# SPISensors.net
KiCad netlist of a schematic drawn in Altium Designer
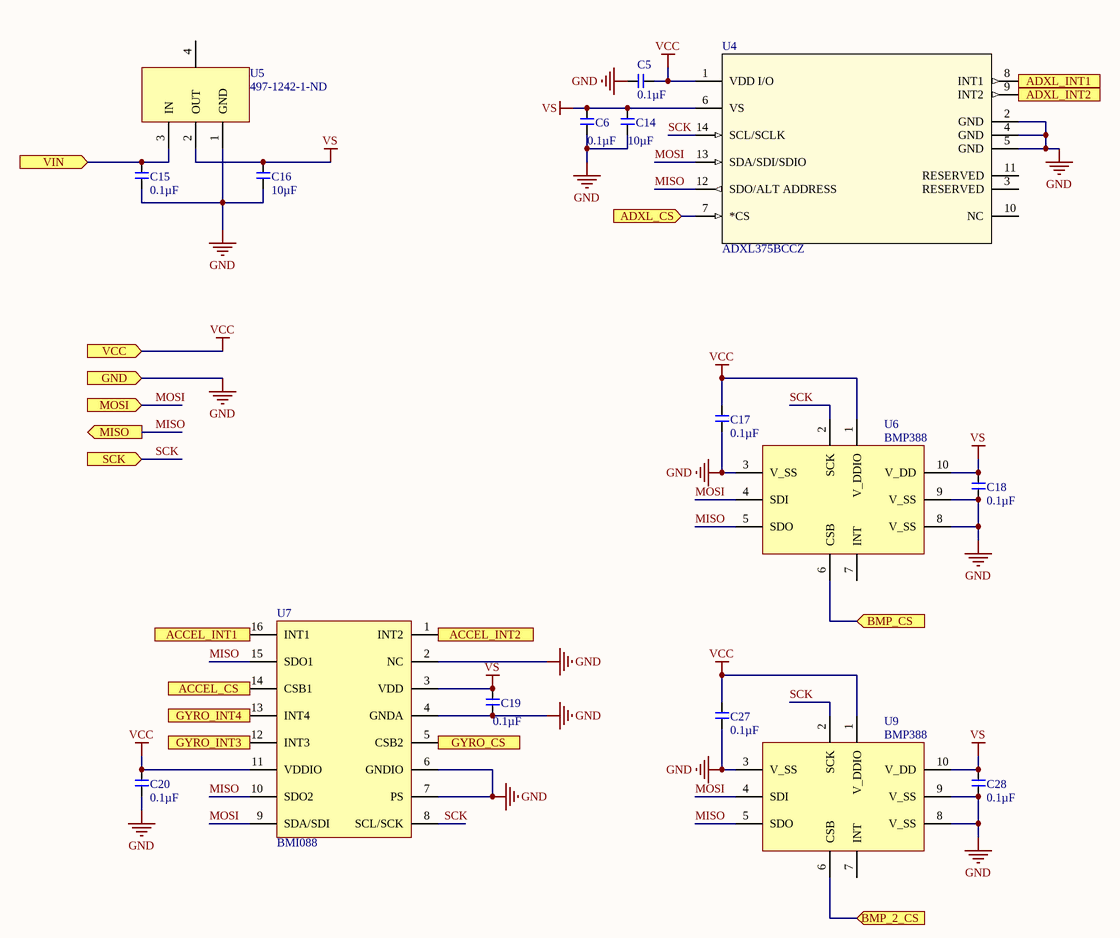
[diagram p0: SPISensors.SchDoc]

(export (version "E")
  (design (tool "Eeschema 10.0.6"))
  (components
    (comp (ref "C5")
      (value "__template_cap")
      (footprint "C0603")
      (fields
        (field (name "CAPACITANCE (SHORTHAND)") "0.1µF")
        (field (name "MANUFACTURER") "Murata Electronics North America")
      )
      (libsource (lib "passives") (part "__template_cap"))
    )
    (comp (ref "C6")
      (value "__template_cap")
      (footprint "C0603")
      (fields
        (field (name "CAPACITANCE (SHORTHAND)") "0.1µF")
        (field (name "MANUFACTURER") "Murata Electronics North America")
      )
      (libsource (lib "passives") (part "__template_cap"))
    )
    (comp (ref "C14")
      (value "__template_cap")
      (footprint "C0603")
      (fields
        (field (name "CAPACITANCE (SHORTHAND)") "10µF")
        (field (name "MANUFACTURER") "Murata Electronics North America")
      )
      (libsource (lib "passives") (part "__template_cap"))
    )
    (comp (ref "C15")
      (value "__template_cap")
      (footprint "C0603")
      (fields
        (field (name "CAPACITANCE (SHORTHAND)") "0.1µF")
        (field (name "MANUFACTURER") "Murata Electronics North America")
      )
      (libsource (lib "passives") (part "__template_cap"))
    )
    (comp (ref "C16")
      (value "__template_cap")
      (footprint "C0603")
      (fields
        (field (name "CAPACITANCE (SHORTHAND)") "10µF")
        (field (name "MANUFACTURER") "Murata Electronics North America")
      )
      (libsource (lib "passives") (part "__template_cap"))
    )
    (comp (ref "C17")
      (value "__template_cap")
      (footprint "C0603")
      (fields
        (field (name "CAPACITANCE (SHORTHAND)") "0.1µF")
        (field (name "MANUFACTURER") "Murata Electronics North America")
      )
      (libsource (lib "passives") (part "__template_cap"))
    )
    (comp (ref "C18")
      (value "__template_cap")
      (footprint "C0603")
      (fields
        (field (name "CAPACITANCE (SHORTHAND)") "0.1µF")
        (field (name "MANUFACTURER") "Murata Electronics North America")
      )
      (libsource (lib "passives") (part "__template_cap"))
    )
    (comp (ref "C19")
      (value "__template_cap")
      (footprint "C0603")
      (fields
        (field (name "CAPACITANCE (SHORTHAND)") "0.1µF")
        (field (name "MANUFACTURER") "Murata Electronics North America")
      )
      (libsource (lib "passives") (part "__template_cap"))
    )
    (comp (ref "C20")
      (value "__template_cap")
      (footprint "C0603")
      (fields
        (field (name "CAPACITANCE (SHORTHAND)") "0.1µF")
        (field (name "MANUFACTURER") "Murata Electronics North America")
      )
      (libsource (lib "passives") (part "__template_cap"))
    )
    (comp (ref "C27")
      (value "__template_cap")
      (footprint "C0603")
      (fields
        (field (name "CAPACITANCE (SHORTHAND)") "0.1µF")
        (field (name "MANUFACTURER") "Murata Electronics North America")
      )
      (libsource (lib "passives") (part "__template_cap"))
    )
    (comp (ref "C28")
      (value "__template_cap")
      (footprint "C0603")
      (fields
        (field (name "CAPACITANCE (SHORTHAND)") "0.1µF")
        (field (name "MANUFACTURER") "Murata Electronics North America")
      )
      (libsource (lib "passives") (part "__template_cap"))
    )
    (comp (ref "U4")
      (value "ADXL375BCCZ")
      (footprint "LGA_CC-14-1")
      (description "200G Accelcerometer")
      (libsource (lib "SSI") (part "ADXL375BCCZ"))
    )
    (comp (ref "U5")
      (value "REG102GA-3.3")
      (footprint "4SOT223")
      (description "IC VOLTAGE REG 3.3V 800MA SOT223")
      (fields
        (field (name "MANUFACTURER") "STMicroelectronics")
        (field (name "MANUFACTURER PART NUMBER") "LD1117S33TR")
        (field (name "SUPPLIER PART NUMBER 1") "497-1242-1-ND")
      )
      (libsource (lib "SSI") (part "LDO_LD1117S33TR"))
    )
    (comp (ref "U6")
      (value "BMP388")
      (footprint "8 pin LGA")
      (description "Pressure Sensor 4.35 PSI ~ 18.13 PSI (30 kPa ~ 125 kPa) Absolute 10-WFLGA")
      (fields (field (name "MANUFACTURER") "Bosch Sensortec"))
      (libsource (lib "SSI") (part "BMP388"))
    )
    (comp (ref "U7")
      (value "BMI088")
      (footprint "BMI088")
      (description "Bosch BMI088")
      (libsource (lib "sensor") (part "IMU_BMI088"))
    )
    (comp (ref "U9")
      (value "BMP388")
      (footprint "8 pin LGA")
      (description "Pressure Sensor 4.35 PSI ~ 18.13 PSI (30 kPa ~ 125 kPa) Absolute 10-WFLGA")
      (fields (field (name "MANUFACTURER") "Bosch Sensortec"))
      (libsource (lib "SSI") (part "BMP388"))
    )
  )
  (nets
    (net (code "1") (name "/ACCEL_CS") (class "Default")
      (node (ref "U7") (pin "14") (pinfunction "CSB1_14") (pintype "passive"))
    )
    (net (code "2") (name "/ACCEL_INT1") (class "Default")
      (node (ref "U7") (pin "16") (pinfunction "INT1_16") (pintype "passive"))
    )
    (net (code "3") (name "/ACCEL_INT2") (class "Default")
      (node (ref "U7") (pin "1") (pinfunction "INT2_1") (pintype "passive"))
    )
    (net (code "4") (name "/ADXL_CS") (class "Default")
      (node (ref "U4") (pin "7") (pinfunction "*CS_7") (pintype "input"))
    )
    (net (code "5") (name "/ADXL_INT1") (class "Default")
      (node (ref "U4") (pin "8") (pinfunction "INT1_8") (pintype "output"))
    )
    (net (code "6") (name "/ADXL_INT2") (class "Default")
      (node (ref "U4") (pin "9") (pinfunction "INT2_9") (pintype "output"))
    )
    (net (code "7") (name "/BMP_2_CS") (class "Default")
      (node (ref "U9") (pin "6") (pinfunction "CSB_6") (pintype "passive"))
    )
    (net (code "8") (name "/BMP_CS") (class "Default")
      (node (ref "U6") (pin "6") (pinfunction "CSB_6") (pintype "passive"))
    )
    (net (code "9") (name "/GYRO_CS") (class "Default")
      (node (ref "U7") (pin "5") (pinfunction "CSB2_5") (pintype "passive"))
    )
    (net (code "10") (name "/GYRO_INT3") (class "Default")
      (node (ref "U7") (pin "12") (pinfunction "INT3_12") (pintype "passive"))
    )
    (net (code "11") (name "/GYRO_INT4") (class "Default")
      (node (ref "U7") (pin "13") (pinfunction "INT4_13") (pintype "passive"))
    )
    (net (code "12") (name "/MISO") (class "Default")
      (node (ref "U4") (pin "12") (pinfunction "SDO/ALT_ADDRESS_12") (pintype "output"))
      (node (ref "U6") (pin "5") (pinfunction "SDO_5") (pintype "passive"))
      (node (ref "U7") (pin "10") (pinfunction "SDO2_10") (pintype "passive"))
      (node (ref "U7") (pin "15") (pinfunction "SDO1_15") (pintype "passive"))
      (node (ref "U9") (pin "5") (pinfunction "SDO_5") (pintype "passive"))
    )
    (net (code "13") (name "/MOSI") (class "Default")
      (node (ref "U4") (pin "13") (pinfunction "SDA/SDI/SDIO_13") (pintype "input"))
      (node (ref "U6") (pin "4") (pinfunction "SDI_4") (pintype "passive"))
      (node (ref "U7") (pin "9") (pinfunction "SDA/SDI_9") (pintype "passive"))
      (node (ref "U9") (pin "4") (pinfunction "SDI_4") (pintype "passive"))
    )
    (net (code "14") (name "/SCK") (class "Default")
      (node (ref "U4") (pin "14") (pinfunction "SCL/SCLK_14") (pintype "input"))
      (node (ref "U6") (pin "2") (pinfunction "SCK_2") (pintype "passive"))
      (node (ref "U7") (pin "8") (pinfunction "SCL/SCK_8") (pintype "passive"))
      (node (ref "U9") (pin "2") (pinfunction "SCK_2") (pintype "passive"))
    )
    (net (code "15") (name "/VIN") (class "Default")
      (node (ref "C15") (pin "1") (pintype "passive"))
      (node (ref "U5") (pin "3") (pinfunction "IN_3") (pintype "passive"))
    )
    (net (code "16") (name "GND") (class "Default")
      (node (ref "C14") (pin "2") (pintype "passive"))
      (node (ref "C15") (pin "2") (pintype "passive"))
      (node (ref "C16") (pin "2") (pintype "passive"))
      (node (ref "C17") (pin "2") (pintype "passive"))
      (node (ref "C18") (pin "2") (pintype "passive"))
      (node (ref "C19") (pin "2") (pintype "passive"))
      (node (ref "C20") (pin "2") (pintype "passive"))
      (node (ref "C27") (pin "2") (pintype "passive"))
      (node (ref "C28") (pin "2") (pintype "passive"))
      (node (ref "C5") (pin "2") (pintype "passive"))
      (node (ref "C6") (pin "1") (pintype "passive"))
      (node (ref "U4") (pin "2") (pinfunction "GND_2") (pintype "power_in"))
      (node (ref "U4") (pin "4") (pinfunction "GND_4") (pintype "power_in"))
      (node (ref "U4") (pin "5") (pinfunction "GND_5") (pintype "power_in"))
      (node (ref "U5") (pin "1") (pinfunction "GND_1") (pintype "passive"))
      (node (ref "U6") (pin "3") (pinfunction "V_SS_3") (pintype "passive"))
      (node (ref "U6") (pin "8") (pinfunction "V_SS_8") (pintype "passive"))
      (node (ref "U6") (pin "9") (pinfunction "V_SS_9") (pintype "passive"))
      (node (ref "U7") (pin "2") (pinfunction "NC_2") (pintype "passive"))
      (node (ref "U7") (pin "4") (pinfunction "GNDA_4") (pintype "passive"))
      (node (ref "U7") (pin "6") (pinfunction "GNDIO_6") (pintype "passive"))
      (node (ref "U7") (pin "7") (pinfunction "PS_7") (pintype "passive"))
      (node (ref "U9") (pin "3") (pinfunction "V_SS_3") (pintype "passive"))
      (node (ref "U9") (pin "8") (pinfunction "V_SS_8") (pintype "passive"))
      (node (ref "U9") (pin "9") (pinfunction "V_SS_9") (pintype "passive"))
    )
    (net (code "17") (name "VCC") (class "Default")
      (node (ref "C17") (pin "1") (pintype "passive"))
      (node (ref "C20") (pin "1") (pintype "passive"))
      (node (ref "C27") (pin "1") (pintype "passive"))
      (node (ref "C5") (pin "1") (pintype "passive"))
      (node (ref "U4") (pin "1") (pinfunction "VDD_I/O_1") (pintype "power_in"))
      (node (ref "U6") (pin "1") (pinfunction "V_DDIO_1") (pintype "passive"))
      (node (ref "U7") (pin "11") (pinfunction "VDDIO_11") (pintype "passive"))
      (node (ref "U9") (pin "1") (pinfunction "V_DDIO_1") (pintype "passive"))
    )
    (net (code "18") (name "VS") (class "Default")
      (node (ref "C14") (pin "1") (pintype "passive"))
      (node (ref "C16") (pin "1") (pintype "passive"))
      (node (ref "C18") (pin "1") (pintype "passive"))
      (node (ref "C19") (pin "1") (pintype "passive"))
      (node (ref "C28") (pin "1") (pintype "passive"))
      (node (ref "C6") (pin "2") (pintype "passive"))
      (node (ref "U4") (pin "6") (pinfunction "VS_6") (pintype "power_in"))
      (node (ref "U5") (pin "2") (pinfunction "OUT_2") (pintype "passive"))
      (node (ref "U6") (pin "10") (pinfunction "V_DD_10") (pintype "passive"))
      (node (ref "U7") (pin "3") (pinfunction "VDD_3") (pintype "passive"))
      (node (ref "U9") (pin "10") (pinfunction "V_DD_10") (pintype "passive"))
    )
    (net (code "19") (name "unconnected-(U4-NC-Pad10)") (class "Default")
      (node (ref "U4") (pin "10") (pinfunction "NC_10") (pintype "passive"))
    )
    (net (code "20") (name "unconnected-(U4-RESERVED-Pad3)") (class "Default")
      (node (ref "U4") (pin "3") (pinfunction "RESERVED_3") (pintype "passive"))
    )
    (net (code "21") (name "unconnected-(U4-RESERVED-Pad11)") (class "Default")
      (node (ref "U4") (pin "11") (pinfunction "RESERVED_11") (pintype "passive"))
    )
    (net (code "22") (name "unconnected-(U5-GND-Pad4)") (class "Default")
      (node (ref "U5") (pin "4") (pinfunction "GND_4") (pintype "passive"))
    )
    (net (code "23") (name "unconnected-(U6-INT-Pad7)") (class "Default")
      (node (ref "U6") (pin "7") (pinfunction "INT_7") (pintype "passive"))
    )
    (net (code "24") (name "unconnected-(U9-INT-Pad7)") (class "Default")
      (node (ref "U9") (pin "7") (pinfunction "INT_7") (pintype "passive"))
    )
  )
)
